# PCB-B4LinkMicroS.net
KiCad netlist of a schematic drawn in EAGLE
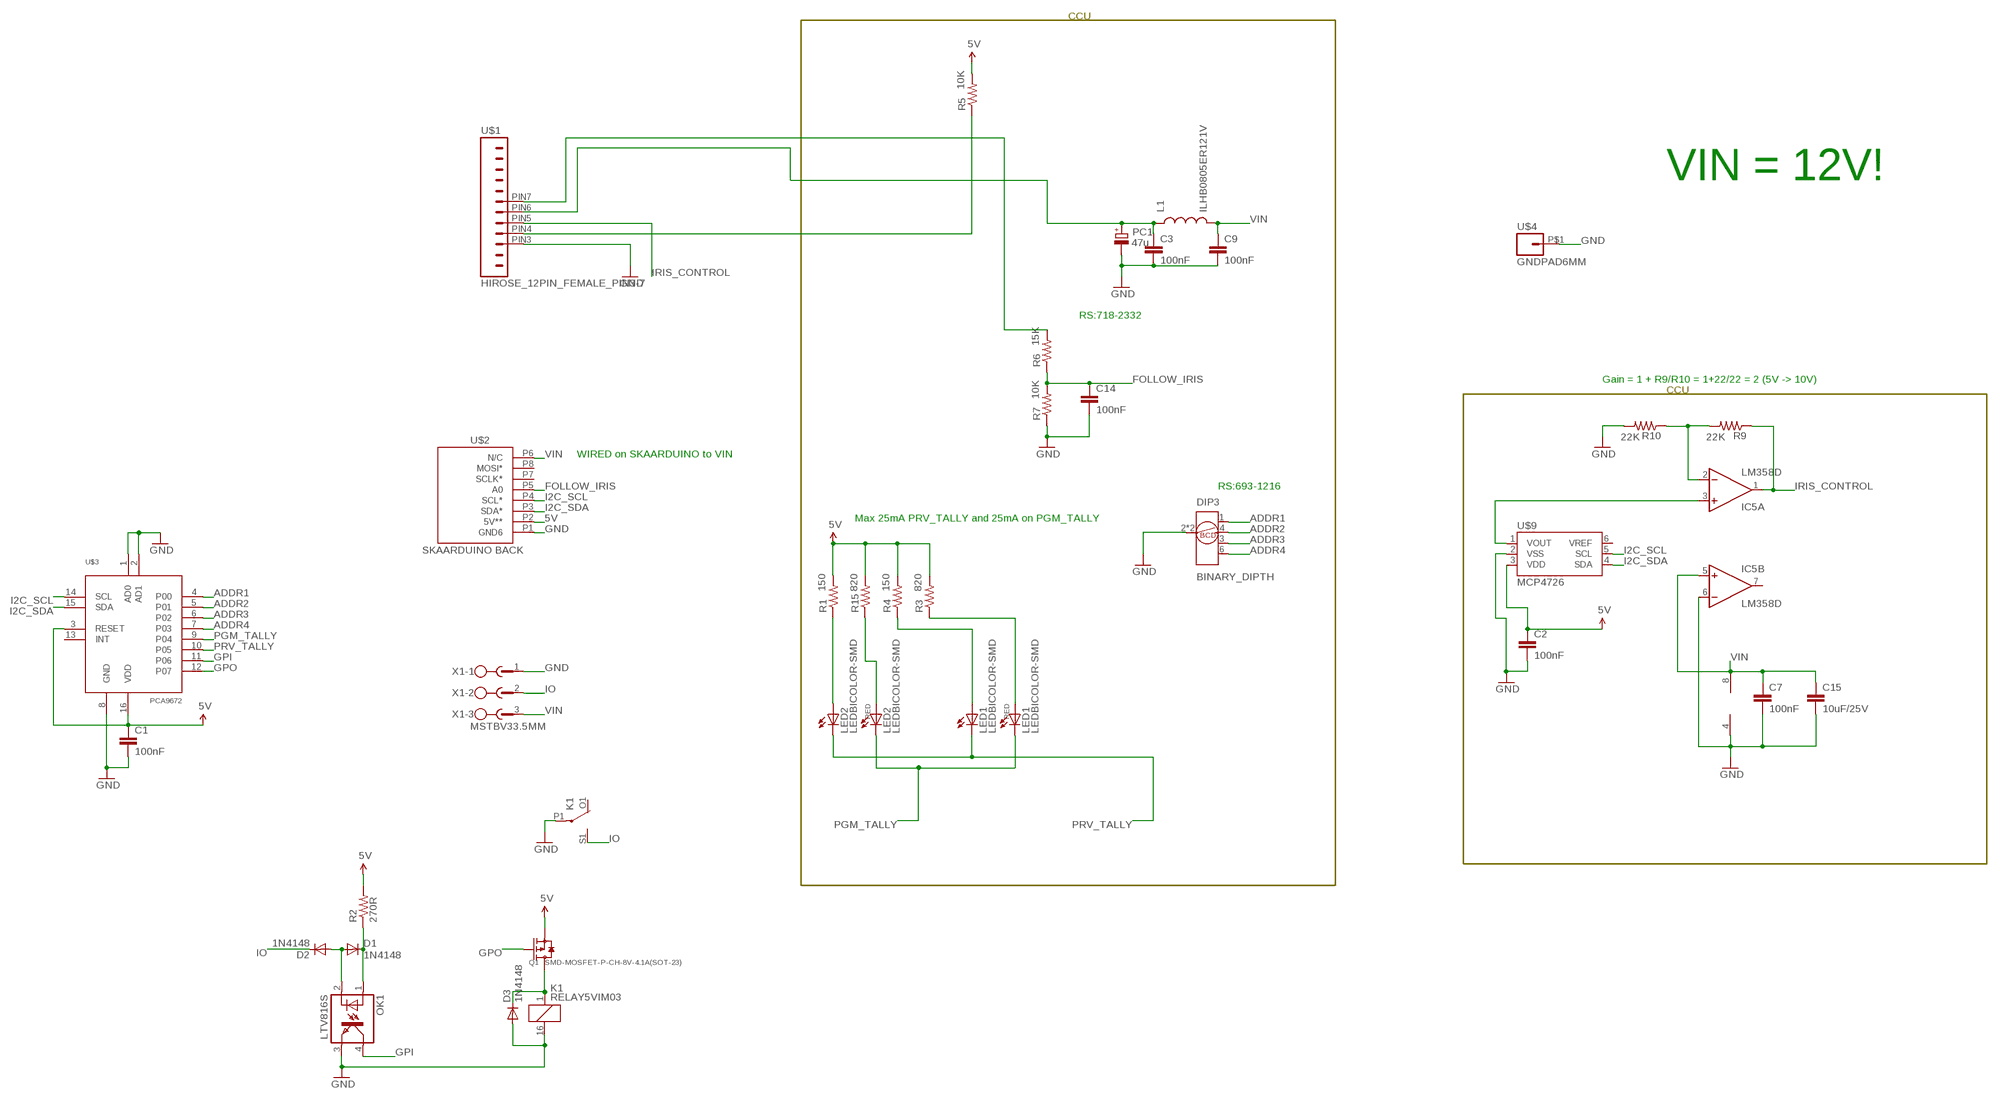
[diagram p0: schematic, sheet 1]

(export (version "E")
  (design (tool "Eeschema 10.0.6"))
  (components
    (comp (ref "C1")
      (value "100nF")
      (footprint "eagle-import:0603-CAP")
      (libsource (lib "eagle-import") (part "CAP0603-CAP"))
    )
    (comp (ref "C2")
      (value "100nF")
      (footprint "eagle-import:0603-CAP")
      (libsource (lib "eagle-import") (part "CAP0603-CAP"))
    )
    (comp (ref "C3")
      (value "100nF")
      (footprint "eagle-import:0603-CAP")
      (libsource (lib "eagle-import") (part "CAP0603-CAP"))
    )
    (comp (ref "C7")
      (value "100nF")
      (footprint "eagle-import:0603-CAP")
      (libsource (lib "eagle-import") (part "CAP0603-CAP"))
    )
    (comp (ref "C9")
      (value "100nF")
      (footprint "eagle-import:0603-CAP")
      (libsource (lib "eagle-import") (part "CAP0603-CAP"))
    )
    (comp (ref "C14")
      (value "100nF")
      (footprint "eagle-import:0603-CAP")
      (libsource (lib "eagle-import") (part "CAP0603-CAP"))
    )
    (comp (ref "C15")
      (value "10uF/25V")
      (footprint "eagle-import:0805")
      (libsource (lib "eagle-import") (part "CAP0805"))
    )
    (comp (ref "D1")
      (value "1N4148")
      (footprint "eagle-import:SOD-323")
      (libsource (lib "eagle-import") (part "DIODESOD"))
    )
    (comp (ref "D2")
      (value "1N4148")
      (footprint "eagle-import:SOD-323")
      (libsource (lib "eagle-import") (part "DIODESOD"))
    )
    (comp (ref "D3")
      (value "1N4148")
      (footprint "eagle-import:SOD-323")
      (libsource (lib "eagle-import") (part "DIODESOD"))
    )
    (comp (ref "DIP3")
      (value "BINARY_DIPTH")
      (footprint "eagle-import:P65TH")
      (libsource (lib "eagle-import") (part "BINARY_DIPTH"))
    )
    (comp (ref "IC5")
      (value "LM358D")
      (footprint "eagle-import:SO08")
      (libsource (lib "eagle-import") (part "LM358D"))
    )
    (comp (ref "K1")
      (value "RELAY5VIM03")
      (footprint "eagle-import:DS2Y")
      (libsource (lib "eagle-import") (part "RELAY5VIM03"))
    )
    (comp (ref "L1")
      (value "ILHB0805ER121V")
      (footprint "eagle-import:0805")
      (libsource (lib "eagle-import") (part "INDUCTOR0805"))
    )
    (comp (ref "LED1")
      (value "LEDBICOLOR-SMD")
      (footprint "eagle-import:LEDBICOLOR-SMD")
      (libsource (lib "eagle-import") (part "LEDBICOLOR-SMD"))
    )
    (comp (ref "LED2")
      (value "LEDBICOLOR-SMD")
      (footprint "eagle-import:LEDBICOLOR-SMD")
      (libsource (lib "eagle-import") (part "LEDBICOLOR-SMD"))
    )
    (comp (ref "OK1")
      (value "LTV816S")
      (footprint "eagle-import:SMD4")
      (libsource (lib "eagle-import") (part "LTV816S"))
    )
    (comp (ref "PC1")
      (value "47u")
      (footprint "eagle-import:PANASONIC_D")
      (libsource (lib "eagle-import") (part "CPOL-EUD"))
    )
    (comp (ref "Q1")
      (value "SMD-MOSFET-P-CH-8V-4.1A(SOT-23)")
      (footprint "eagle-import:SOT-23")
      (fields (field (name "MPN") "CJ2305"))
      (libsource (lib "eagle-import") (part "SMD-MOSFET-P-CH-8V-4.1A(SOT-23)"))
    )
    (comp (ref "R1")
      (value "150")
      (footprint "eagle-import:0603-RES")
      (libsource (lib "eagle-import") (part "RESISTOR0603-RES"))
    )
    (comp (ref "R2")
      (value "270R")
      (footprint "eagle-import:0603-RES")
      (libsource (lib "eagle-import") (part "RESISTOR0603-RES"))
    )
    (comp (ref "R3")
      (value "820")
      (footprint "eagle-import:0603-RES")
      (libsource (lib "eagle-import") (part "RESISTOR0603-RES"))
    )
    (comp (ref "R4")
      (value "150")
      (footprint "eagle-import:0603-RES")
      (libsource (lib "eagle-import") (part "RESISTOR0603-RES"))
    )
    (comp (ref "R5")
      (value "10K")
      (footprint "eagle-import:0603-RES")
      (libsource (lib "eagle-import") (part "RESISTOR0603-RES"))
    )
    (comp (ref "R6")
      (value "15K")
      (footprint "eagle-import:0603-RES")
      (libsource (lib "eagle-import") (part "RESISTOR0603-RES"))
    )
    (comp (ref "R7")
      (value "10K")
      (footprint "eagle-import:0603-RES")
      (libsource (lib "eagle-import") (part "RESISTOR0603-RES"))
    )
    (comp (ref "R9")
      (value "22K")
      (footprint "eagle-import:0603-RES")
      (libsource (lib "eagle-import") (part "RESISTOR0603-RES"))
    )
    (comp (ref "R10")
      (value "22K")
      (footprint "eagle-import:0603-RES")
      (libsource (lib "eagle-import") (part "RESISTOR0603-RES"))
    )
    (comp (ref "R15")
      (value "820")
      (footprint "eagle-import:0603-RES")
      (libsource (lib "eagle-import") (part "RESISTOR0603-RES"))
    )
    (comp (ref "U$1")
      (value "HIROSE_12PIN_FEMALE_PIN3-7")
      (footprint "eagle-import:HIROSE_12PIN_RECEP_LESSHOLES")
      (libsource (lib "eagle-import") (part "HIROSE_12PIN_FEMALE_PIN3-7"))
    )
    (comp (ref "U$2")
      (value "SKAARDUINO_BACK_SERIAL")
      (footprint "eagle-import:SKAARDUINO_BACK_PTH_SERIAL")
      (libsource (lib "eagle-import") (part "SKAARDUINO_BACK_SERIAL"))
    )
    (comp (ref "U$3")
      (value "PCA9672")
      (footprint "eagle-import:TSSOP16")
      (libsource (lib "eagle-import") (part "PCA9672"))
    )
    (comp (ref "U$4")
      (value "GNDPAD6MM")
      (footprint "eagle-import:3.2MMPAD6MM")
      (libsource (lib "eagle-import") (part "GNDPAD6MM"))
    )
    (comp (ref "U$9")
      (value "MCP4726")
      (footprint "eagle-import:SOT23-6L")
      (libsource (lib "eagle-import") (part "MCP4726"))
    )
    (comp (ref "X1")
      (value "MSTBV33.5MM")
      (footprint "eagle-import:MSTBV3-3.5")
      (libsource (lib "eagle-import") (part "MSTBV33.5MM"))
    )
  )
  (nets
    (net (code "1") (name "/ADDR1") (class "Default")
      (node (ref "DIP3") (pin "1") (pinfunction "1_1") (pintype "passive"))
      (node (ref "U$3") (pin "4") (pinfunction "P00_4") (pintype "bidirectional"))
    )
    (net (code "2") (name "/ADDR2") (class "Default")
      (node (ref "DIP3") (pin "4") (pinfunction "2_4") (pintype "passive"))
      (node (ref "U$3") (pin "5") (pinfunction "P01_5") (pintype "bidirectional"))
    )
    (net (code "3") (name "/ADDR3") (class "Default")
      (node (ref "DIP3") (pin "3") (pinfunction "4_3") (pintype "passive"))
      (node (ref "U$3") (pin "6") (pinfunction "P02_6") (pintype "bidirectional"))
    )
    (net (code "4") (name "/ADDR4") (class "Default")
      (node (ref "DIP3") (pin "6") (pinfunction "8_6") (pintype "passive"))
      (node (ref "U$3") (pin "7") (pinfunction "P03_7") (pintype "bidirectional"))
    )
    (net (code "5") (name "/FOLLOW_IRIS") (class "Default")
      (node (ref "C14") (pin "1") (pinfunction "1_1") (pintype "passive"))
      (node (ref "R6") (pin "1") (pinfunction "1_1") (pintype "passive"))
      (node (ref "R7") (pin "2") (pinfunction "2_2") (pintype "passive"))
      (node (ref "U$2") (pin "P5") (pinfunction "A0_P5") (pintype "bidirectional"))
    )
    (net (code "6") (name "/GPI") (class "Default")
      (node (ref "OK1") (pin "4") (pinfunction "COL_4") (pintype "passive"))
      (node (ref "U$3") (pin "11") (pinfunction "P06_11") (pintype "bidirectional"))
    )
    (net (code "7") (name "/GPO") (class "Default")
      (node (ref "Q1") (pin "1") (pinfunction "G_1") (pintype "passive"))
      (node (ref "U$3") (pin "12") (pinfunction "P07_12") (pintype "bidirectional"))
    )
    (net (code "8") (name "/I2C_SCL") (class "Default")
      (node (ref "U$2") (pin "P4") (pinfunction "SCL*_P4") (pintype "bidirectional"))
      (node (ref "U$3") (pin "14") (pinfunction "SCL_14") (pintype "bidirectional"))
      (node (ref "U$9") (pin "5") (pinfunction "SCL_5") (pintype "bidirectional"))
    )
    (net (code "9") (name "/I2C_SDA") (class "Default")
      (node (ref "U$2") (pin "P3") (pinfunction "SDA*_P3") (pintype "bidirectional"))
      (node (ref "U$3") (pin "15") (pinfunction "SDA_15") (pintype "bidirectional"))
      (node (ref "U$9") (pin "4") (pinfunction "SDA_4") (pintype "bidirectional"))
    )
    (net (code "10") (name "/IO") (class "Default")
      (node (ref "D2") (pin "1") (pinfunction "C_1") (pintype "passive"))
      (node (ref "K1") (pin "S1") (pinfunction "S_S1") (pintype "passive"))
      (node (ref "X1") (pin "2") (pinfunction "1_2") (pintype "passive"))
    )
    (net (code "11") (name "/IRIS_CONTROL") (class "Default")
      (node (ref "IC5") (pin "1") (pinfunction "OUT_1") (pintype "output"))
      (node (ref "R9") (pin "1") (pinfunction "1_1") (pintype "passive"))
      (node (ref "U$1") (pin "PIN5") (pinfunction "5_PIN5") (pintype "passive"))
    )
    (net (code "12") (name "/PGM_TALLY") (class "Default")
      (node (ref "LED1") (pin "P$2") (pinfunction "C_P$2") (pintype "passive"))
      (node (ref "LED2") (pin "P$2") (pinfunction "C_P$2") (pintype "passive"))
      (node (ref "U$3") (pin "9") (pinfunction "P04_9") (pintype "bidirectional"))
    )
    (net (code "13") (name "/PRV_TALLY") (class "Default")
      (node (ref "LED1") (pin "P$4") (pinfunction "C1_P$4") (pintype "passive"))
      (node (ref "LED2") (pin "P$4") (pinfunction "C1_P$4") (pintype "passive"))
      (node (ref "U$3") (pin "10") (pinfunction "P05_10") (pintype "bidirectional"))
    )
    (net (code "14") (name "/VIN") (class "Default")
      (node (ref "C15") (pin "1") (pinfunction "1_1") (pintype "passive"))
      (node (ref "C7") (pin "1") (pinfunction "1_1") (pintype "passive"))
      (node (ref "C9") (pin "1") (pinfunction "1_1") (pintype "passive"))
      (node (ref "IC5") (pin "5") (pinfunction "+IN_5") (pintype "input"))
      (node (ref "IC5") (pin "8") (pinfunction "V+_8") (pintype "power_in"))
      (node (ref "L1") (pin "2") (pinfunction "2_2") (pintype "passive"))
      (node (ref "U$2") (pin "P6") (pinfunction "N/C_P6") (pintype "bidirectional"))
      (node (ref "X1") (pin "3") (pinfunction "1_3") (pintype "passive"))
    )
    (net (code "15") (name "5V") (class "Default")
      (node (ref "C1") (pin "1") (pinfunction "1_1") (pintype "passive"))
      (node (ref "C2") (pin "1") (pinfunction "1_1") (pintype "passive"))
      (node (ref "Q1") (pin "2") (pinfunction "S_2") (pintype "passive"))
      (node (ref "R1") (pin "2") (pinfunction "2_2") (pintype "passive"))
      (node (ref "R15") (pin "2") (pinfunction "2_2") (pintype "passive"))
      (node (ref "R2") (pin "2") (pinfunction "2_2") (pintype "passive"))
      (node (ref "R3") (pin "2") (pinfunction "2_2") (pintype "passive"))
      (node (ref "R4") (pin "2") (pinfunction "2_2") (pintype "passive"))
      (node (ref "R5") (pin "2") (pinfunction "2_2") (pintype "passive"))
      (node (ref "U$2") (pin "P2") (pinfunction "5V**_P2") (pintype "power_in"))
      (node (ref "U$3") (pin "16") (pinfunction "VDD_16") (pintype "power_in"))
      (node (ref "U$3") (pin "3") (pinfunction "RESET_3") (pintype "input"))
      (node (ref "U$9") (pin "3") (pinfunction "VDD_3") (pintype "power_in"))
    )
    (net (code "16") (name "GND") (class "Default")
      (node (ref "C1") (pin "2") (pinfunction "2_2") (pintype "passive"))
      (node (ref "C14") (pin "2") (pinfunction "2_2") (pintype "passive"))
      (node (ref "C15") (pin "2") (pinfunction "2_2") (pintype "passive"))
      (node (ref "C2") (pin "2") (pinfunction "2_2") (pintype "passive"))
      (node (ref "C3") (pin "2") (pinfunction "2_2") (pintype "passive"))
      (node (ref "C7") (pin "2") (pinfunction "2_2") (pintype "passive"))
      (node (ref "C9") (pin "2") (pinfunction "2_2") (pintype "passive"))
      (node (ref "D3") (pin "2") (pinfunction "A_2") (pintype "passive"))
      (node (ref "DIP3") (pin "2") (pinfunction "GND_2") (pintype "passive"))
      (node (ref "DIP3") (pin "5") (pinfunction "GND_5") (pintype "passive"))
      (node (ref "IC5") (pin "4") (pinfunction "V-_4") (pintype "power_in"))
      (node (ref "IC5") (pin "6") (pinfunction "-IN_6") (pintype "input"))
      (node (ref "K1") (pin "16") (pinfunction "2_16") (pintype "passive"))
      (node (ref "K1") (pin "P1") (pinfunction "P_P1") (pintype "passive"))
      (node (ref "OK1") (pin "3") (pinfunction "EMIT_3") (pintype "passive"))
      (node (ref "PC1") (pin "-") (pinfunction "-_-") (pintype "passive"))
      (node (ref "R10") (pin "2") (pinfunction "2_2") (pintype "passive"))
      (node (ref "R7") (pin "1") (pinfunction "1_1") (pintype "passive"))
      (node (ref "U$1") (pin "PIN3") (pinfunction "3_PIN3") (pintype "passive"))
      (node (ref "U$2") (pin "P1") (pinfunction "GND6_P1") (pintype "power_in"))
      (node (ref "U$3") (pin "1") (pinfunction "AD0_1") (pintype "input"))
      (node (ref "U$3") (pin "2") (pinfunction "AD1_2") (pintype "input"))
      (node (ref "U$3") (pin "8") (pinfunction "GND_8") (pintype "power_in"))
      (node (ref "U$4") (pin "P$1") (pinfunction "1_P$1") (pintype "passive"))
      (node (ref "U$9") (pin "2") (pinfunction "VSS_2") (pintype "power_in"))
      (node (ref "X1") (pin "1") (pinfunction "1_1") (pintype "passive"))
    )
    (net (code "17") (name "Net-(D1-A)") (class "Default")
      (node (ref "D1") (pin "2") (pinfunction "A_2") (pintype "passive"))
      (node (ref "D2") (pin "2") (pinfunction "A_2") (pintype "passive"))
      (node (ref "OK1") (pin "2") (pinfunction "C_2") (pintype "passive"))
    )
    (net (code "18") (name "Net-(D1-C)") (class "Default")
      (node (ref "D1") (pin "1") (pinfunction "C_1") (pintype "passive"))
      (node (ref "OK1") (pin "1") (pinfunction "A_1") (pintype "passive"))
      (node (ref "R2") (pin "1") (pinfunction "1_1") (pintype "passive"))
    )
    (net (code "19") (name "Net-(D3-C)") (class "Default")
      (node (ref "D3") (pin "1") (pinfunction "C_1") (pintype "passive"))
      (node (ref "K1") (pin "1") (pinfunction "1_1") (pintype "passive"))
      (node (ref "Q1") (pin "3") (pinfunction "D_3") (pintype "passive"))
    )
    (net (code "20") (name "Net-(IC5A-+IN)") (class "Default")
      (node (ref "IC5") (pin "3") (pinfunction "+IN_3") (pintype "input"))
      (node (ref "U$9") (pin "1") (pinfunction "VOUT_1") (pintype "output"))
    )
    (net (code "21") (name "Net-(IC5A--IN)") (class "Default")
      (node (ref "IC5") (pin "2") (pinfunction "-IN_2") (pintype "input"))
      (node (ref "R10") (pin "1") (pinfunction "1_1") (pintype "passive"))
      (node (ref "R9") (pin "2") (pinfunction "2_2") (pintype "passive"))
    )
    (net (code "22") (name "Net-(LED1-A)") (class "Default")
      (node (ref "LED1") (pin "P$1") (pinfunction "A_P$1") (pintype "passive"))
      (node (ref "R3") (pin "1") (pinfunction "1_1") (pintype "passive"))
    )
    (net (code "23") (name "Net-(LED1-A1)") (class "Default")
      (node (ref "LED1") (pin "P$3") (pinfunction "A1_P$3") (pintype "passive"))
      (node (ref "R4") (pin "1") (pinfunction "1_1") (pintype "passive"))
    )
    (net (code "24") (name "Net-(LED2-A)") (class "Default")
      (node (ref "LED2") (pin "P$1") (pinfunction "A_P$1") (pintype "passive"))
      (node (ref "R15") (pin "1") (pinfunction "1_1") (pintype "passive"))
    )
    (net (code "25") (name "Net-(LED2-A1)") (class "Default")
      (node (ref "LED2") (pin "P$3") (pinfunction "A1_P$3") (pintype "passive"))
      (node (ref "R1") (pin "1") (pinfunction "1_1") (pintype "passive"))
    )
    (net (code "26") (name "Net-(U$1-4)") (class "Default")
      (node (ref "R5") (pin "1") (pinfunction "1_1") (pintype "passive"))
      (node (ref "U$1") (pin "PIN4") (pinfunction "4_PIN4") (pintype "passive"))
    )
    (net (code "27") (name "Net-(U$1-6)") (class "Default")
      (node (ref "C3") (pin "1") (pinfunction "1_1") (pintype "passive"))
      (node (ref "L1") (pin "1") (pinfunction "1_1") (pintype "passive"))
      (node (ref "PC1") (pin "+") (pinfunction "+_+") (pintype "passive"))
      (node (ref "U$1") (pin "PIN6") (pinfunction "6_PIN6") (pintype "passive"))
    )
    (net (code "28") (name "Net-(U$1-7)") (class "Default")
      (node (ref "R6") (pin "2") (pinfunction "2_2") (pintype "passive"))
      (node (ref "U$1") (pin "PIN7") (pinfunction "7_PIN7") (pintype "passive"))
    )
    (net (code "29") (name "unconnected-(IC5B-OUT-Pad7)") (class "Default")
      (node (ref "IC5") (pin "7") (pinfunction "OUT_7") (pintype "output"))
    )
    (net (code "30") (name "unconnected-(K1B-O-PadO1)") (class "Default")
      (node (ref "K1") (pin "O1") (pinfunction "O_O1") (pintype "passive"))
    )
    (net (code "31") (name "unconnected-(U$2-MOSI*-PadP8)") (class "Default")
      (node (ref "U$2") (pin "P8") (pinfunction "MOSI*_P8") (pintype "output"))
    )
    (net (code "32") (name "unconnected-(U$2-SCLK*-PadP7)") (class "Default")
      (node (ref "U$2") (pin "P7") (pinfunction "SCLK*_P7") (pintype "output"))
    )
    (net (code "33") (name "unconnected-(U$3-INT-Pad13)") (class "Default")
      (node (ref "U$3") (pin "13") (pinfunction "INT_13") (pintype "output"))
    )
    (net (code "34") (name "unconnected-(U$9-VREF-Pad6)") (class "Default")
      (node (ref "U$9") (pin "6") (pinfunction "VREF_6") (pintype "input"))
    )
  )
)
